# RefVolt.net
KiCad netlist of a schematic drawn in EAGLE
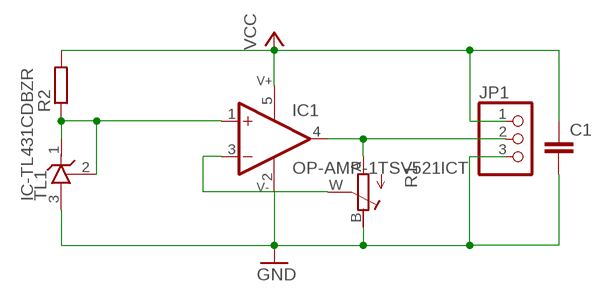
[diagram p0: schematic, sheet 1]

(export (version "E")
  (design (tool "Eeschema 10.0.6"))
  (components
    (comp (ref "C1")
      (value "CAP_0805")
      (footprint "eagle-import:C0805")
      (libsource (lib "eagle-import") (part "CAP_0805"))
    )
    (comp (ref "IC1")
      (value "OP-AMP-1TSV521ICT")
      (footprint "eagle-import:SC70-5L")
      (libsource (lib "eagle-import") (part "OP-AMP-1TSV521ICT"))
    )
    (comp (ref "JP1")
      (value "PINHD-1X3/90")
      (footprint "eagle-import:1X03_90")
      (libsource (lib "eagle-import") (part "PINHD-1X3/90"))
    )
    (comp (ref "R1")
      (value "R_POTTURN-X")
      (footprint "eagle-import:RJ9W")
      (libsource (lib "eagle-import") (part "R_POTTURN-X"))
    )
    (comp (ref "R2")
      (value "R_0805")
      (footprint "eagle-import:R0805")
      (libsource (lib "eagle-import") (part "R_0805"))
    )
    (comp (ref "TL1")
      (value "IC-TL431CDBZR")
      (footprint "eagle-import:SOT23")
      (libsource (lib "eagle-import") (part "IC-TL431CDBZR"))
    )
  )
  (nets
    (net (code "1") (name "GND") (class "Default")
      (node (ref "C1") (pin "2") (pinfunction "2_2") (pintype "passive"))
      (node (ref "IC1") (pin "2") (pinfunction "V-_2") (pintype "power_in"))
      (node (ref "JP1") (pin "3") (pinfunction "3_3") (pintype "passive"))
      (node (ref "R1") (pin "B") (pinfunction "E_B") (pintype "passive"))
      (node (ref "TL1") (pin "3") (pinfunction "A_3") (pintype "passive"))
    )
    (net (code "2") (name "Net-(IC1A-+IN)") (class "Default")
      (node (ref "IC1") (pin "1") (pinfunction "+IN_1") (pintype "input"))
      (node (ref "R2") (pin "1") (pinfunction "1_1") (pintype "passive"))
      (node (ref "TL1") (pin "1") (pinfunction "C_1") (pintype "passive"))
      (node (ref "TL1") (pin "2") (pinfunction "R_2") (pintype "passive"))
    )
    (net (code "3") (name "Net-(IC1A--IN)") (class "Default")
      (node (ref "IC1") (pin "3") (pinfunction "-IN_3") (pintype "input"))
      (node (ref "R1") (pin "W") (pinfunction "S_W") (pintype "passive"))
    )
    (net (code "4") (name "Net-(IC1A-OUT)") (class "Default")
      (node (ref "IC1") (pin "4") (pinfunction "OUT_4") (pintype "output"))
      (node (ref "JP1") (pin "2") (pinfunction "2_2") (pintype "passive"))
      (node (ref "R1") (pin "A") (pinfunction "A_A") (pintype "passive"))
    )
    (net (code "5") (name "VCC") (class "Default")
      (node (ref "C1") (pin "1") (pinfunction "1_1") (pintype "passive"))
      (node (ref "IC1") (pin "5") (pinfunction "V+_5") (pintype "power_in"))
      (node (ref "JP1") (pin "1") (pinfunction "1_1") (pintype "passive"))
      (node (ref "R2") (pin "2") (pinfunction "2_2") (pintype "passive"))
    )
  )
)
